# inga_charger.net
KiCad netlist of a schematic drawn in EAGLE
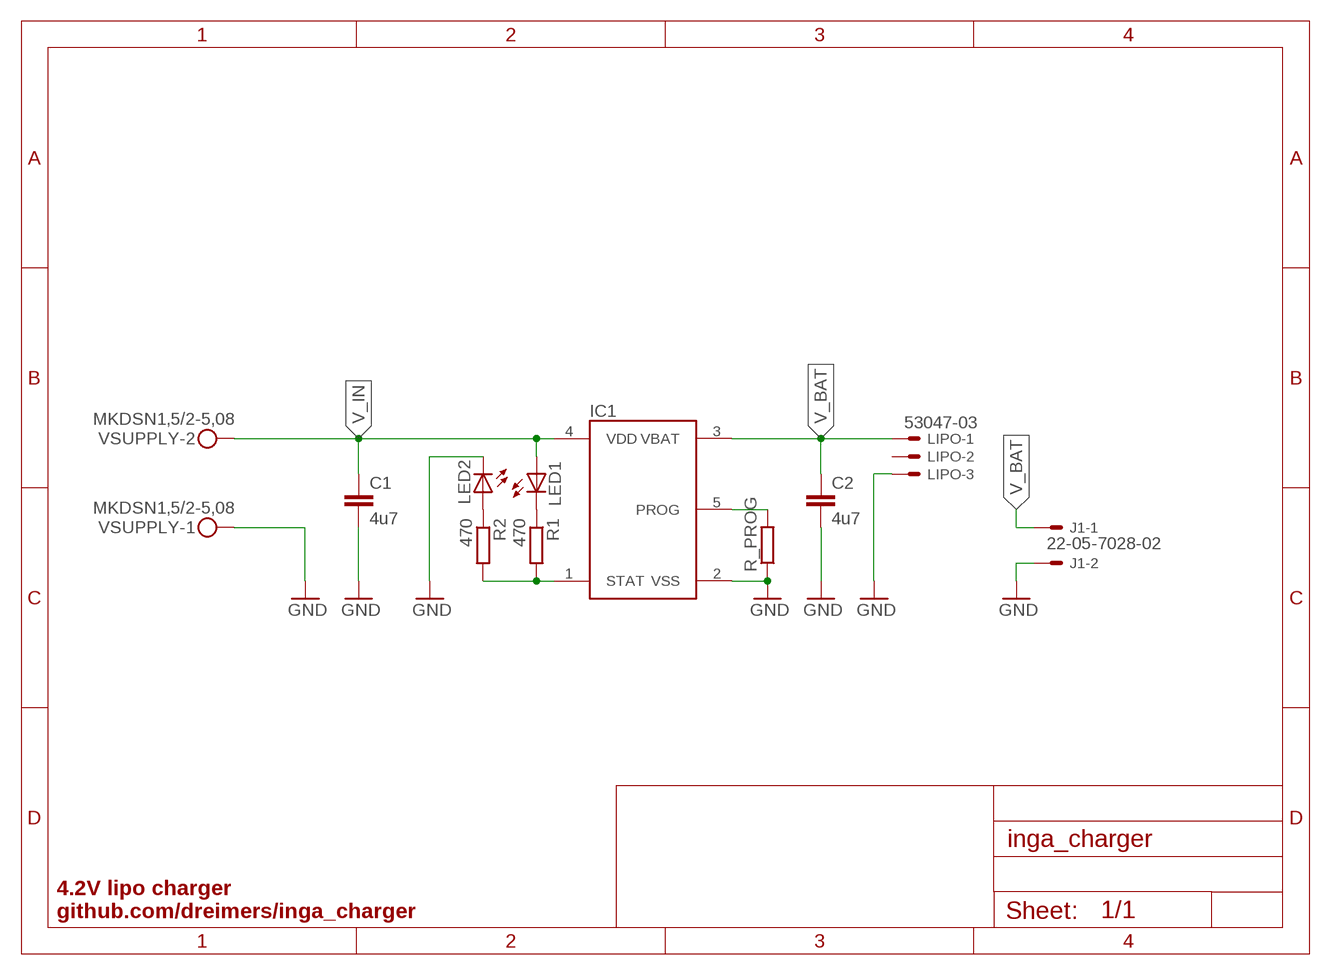
[diagram p0: schematic, sheet 1]

(export (version "E")
  (design (tool "Eeschema 10.0.6"))
  (components
    (comp (ref "C1")
      (value "4u7")
      (footprint "eagle-import:C0805")
      (libsource (lib "eagle-import") (part "C-EUC0805"))
    )
    (comp (ref "C2")
      (value "4u7")
      (footprint "eagle-import:C0805")
      (libsource (lib "eagle-import") (part "C-EUC0805"))
    )
    (comp (ref "IC1")
      (value "MCP73831/2")
      (footprint "eagle-import:SOT23-5")
      (libsource (lib "eagle-import") (part "MCP73831/2"))
    )
    (comp (ref "J1")
      (value "22-05-7028-02")
      (footprint "eagle-import:7395-02")
      (libsource (lib "eagle-import") (part "22-?-0205-7028"))
    )
    (comp (ref "LED1")
      (value "LEDCHIP-LED0603")
      (footprint "eagle-import:CHIP-LED0603")
      (libsource (lib "eagle-import") (part "LEDCHIP-LED0603"))
    )
    (comp (ref "LED2")
      (value "LEDCHIP-LED0603")
      (footprint "eagle-import:CHIP-LED0603")
      (libsource (lib "eagle-import") (part "LEDCHIP-LED0603"))
    )
    (comp (ref "LIPO")
      (value "53047-03")
      (footprint "eagle-import:53047-03")
      (fields (field (name "MPN") "530470310"))
      (libsource (lib "eagle-import") (part "53?-03047"))
    )
    (comp (ref "R1")
      (value "470")
      (footprint "eagle-import:R0402")
      (libsource (lib "eagle-import") (part "R-EU_R0402"))
    )
    (comp (ref "R2")
      (value "470")
      (footprint "eagle-import:R0402")
      (libsource (lib "eagle-import") (part "R-EU_R0402"))
    )
    (comp (ref "R_PROG")
      (value "R-EU_R0603")
      (footprint "eagle-import:R0603")
      (libsource (lib "eagle-import") (part "R-EU_R0603"))
    )
    (comp (ref "VSUPPLY")
      (value "MKDSN1,5/2-5,08")
      (footprint "eagle-import:MKDSN1,5_2-5,08")
      (libsource (lib "eagle-import") (part "MKDSN1,5/2-5,08"))
    )
  )
  (nets
    (net (code "1") (name "GND") (class "Default")
      (node (ref "C1") (pin "2") (pinfunction "2_2") (pintype "passive"))
      (node (ref "C2") (pin "2") (pinfunction "2_2") (pintype "passive"))
      (node (ref "IC1") (pin "2") (pinfunction "VSS_2") (pintype "bidirectional"))
      (node (ref "J1") (pin "2") (pinfunction "S_2") (pintype "passive"))
      (node (ref "LED2") (pin "C") (pinfunction "C_C") (pintype "passive"))
      (node (ref "LIPO") (pin "3") (pinfunction "S_3") (pintype "passive"))
      (node (ref "R_PROG") (pin "1") (pinfunction "1_1") (pintype "passive"))
      (node (ref "VSUPPLY") (pin "1") (pinfunction "KL_1") (pintype "passive"))
    )
    (net (code "2") (name "Net-(IC1-PROG)") (class "Default")
      (node (ref "IC1") (pin "5") (pinfunction "PROG_5") (pintype "bidirectional"))
      (node (ref "R_PROG") (pin "2") (pinfunction "2_2") (pintype "passive"))
    )
    (net (code "3") (name "Net-(IC1-STAT)") (class "Default")
      (node (ref "IC1") (pin "1") (pinfunction "STAT_1") (pintype "bidirectional"))
      (node (ref "R1") (pin "2") (pinfunction "2_2") (pintype "passive"))
      (node (ref "R2") (pin "2") (pinfunction "2_2") (pintype "passive"))
    )
    (net (code "4") (name "Net-(LED1-PadC)") (class "Default")
      (node (ref "LED1") (pin "C") (pinfunction "C_C") (pintype "passive"))
      (node (ref "R1") (pin "1") (pinfunction "1_1") (pintype "passive"))
    )
    (net (code "5") (name "Net-(LED2-PadA)") (class "Default")
      (node (ref "LED2") (pin "A") (pinfunction "A_A") (pintype "passive"))
      (node (ref "R2") (pin "1") (pinfunction "1_1") (pintype "passive"))
    )
    (net (code "6") (name "V_BAT") (class "Default")
      (node (ref "C2") (pin "1") (pinfunction "1_1") (pintype "passive"))
      (node (ref "IC1") (pin "3") (pinfunction "VBAT_3") (pintype "bidirectional"))
      (node (ref "J1") (pin "1") (pinfunction "S_1") (pintype "passive"))
      (node (ref "LIPO") (pin "1") (pinfunction "S_1") (pintype "passive"))
    )
    (net (code "7") (name "V_IN") (class "Default")
      (node (ref "C1") (pin "1") (pinfunction "1_1") (pintype "passive"))
      (node (ref "IC1") (pin "4") (pinfunction "VDD_4") (pintype "bidirectional"))
      (node (ref "LED1") (pin "A") (pinfunction "A_A") (pintype "passive"))
      (node (ref "VSUPPLY") (pin "2") (pinfunction "KL_2") (pintype "passive"))
    )
    (net (code "8") (name "unconnected-(LIPOB-S-Pad2)") (class "Default")
      (node (ref "LIPO") (pin "2") (pinfunction "S_2") (pintype "passive"))
    )
  )
)
